# USB_OTG_FS.net
KiCad netlist of a schematic drawn in Altium Designer
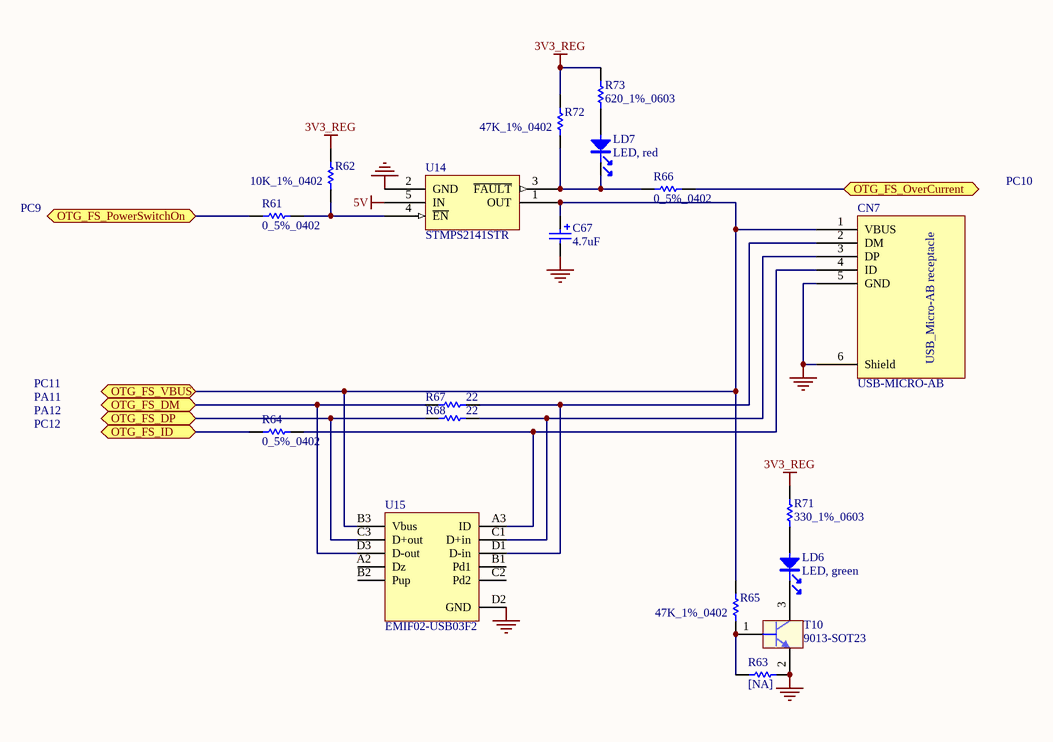
[diagram p0: USB_OTG_FS.SchDoc]

(export (version "E")
  (design (tool "Eeschema 10.0.6"))
  (components
    (comp (ref "C67")
      (value "4.7uF")
      (footprint "TAN-A")
      (description "Polarized Capacitor,4.7uF,16V,10%,typeA,AVX")
      (libsource (lib "MCD_TOOLS") (part "Cap_4.7uF_POL_10%_TANA"))
    )
    (comp (ref "CN7")
      (value "USB-MICRO-AB")
      (footprint "USB-MICRO-AB")
      (description "USB-MICRO-AB, 47590-0001, SMT, MOLEX")
      (libsource (lib "MCD_TOOLS") (part "USB-MICRO-AB"))
    )
    (comp (ref "LD6")
      (value "LED, green")
      (footprint "0603D")
      (description "LED,green,0603,19-213SYGC/S530-E2/TR8,everlight")
      (libsource (lib "MCD_TOOLS") (part "LED_green"))
    )
    (comp (ref "LD7")
      (value "LED, red")
      (footprint "0603D")
      (description "LED,red,0603,19-213-R6C-AP1Q2B/3T,everlight")
      (libsource (lib "MCD_TOOLS") (part "LED_red"))
    )
    (comp (ref "R61")
      (value "0_5%_0402")
      (footprint "0402R")
      (description "Resistor,0,0402,5%,YAGEO")
      (libsource (lib "MCD_TOOLS") (part "Res_0_5%_0402"))
    )
    (comp (ref "R62")
      (value "10K_1%_0402")
      (footprint "0402R")
      (description "Resistor,10K,0402,1%,YAGEO")
      (libsource (lib "MCD_TOOLS") (part "Res_10K_1%_0402"))
    )
    (comp (ref "R63")
      (value "[NA]")
      (footprint "0402R")
      (description "Resistor,[NA],0402")
      (libsource (lib "MCD_TOOLS") (part "Res_NA_0402"))
    )
    (comp (ref "R64")
      (value "0_5%_0402")
      (footprint "0402R")
      (description "Resistor,0,0402,5%,YAGEO")
      (libsource (lib "MCD_TOOLS") (part "Res_0_5%_0402"))
    )
    (comp (ref "R65")
      (value "47K_1%_0402")
      (footprint "0402R")
      (description "Resistor,47K,0402,1%,YAGEO")
      (libsource (lib "MCD_TOOLS") (part "Res_47K_1%_0402"))
    )
    (comp (ref "R66")
      (value "0_5%_0402")
      (footprint "0402R")
      (description "Resistor,0,0402,5%,YAGEO")
      (libsource (lib "MCD_TOOLS") (part "Res_0_5%_0402"))
    )
    (comp (ref "R67")
      (value "22")
      (footprint "0402R")
      (description "Resistor")
      (fields (field (name "PUBLISHER") "Altium Limited"))
      (libsource (lib "Miscellaneous Devices") (part "Res1"))
    )
    (comp (ref "R68")
      (value "22")
      (footprint "0402R")
      (description "Resistor")
      (fields (field (name "PUBLISHER") "Altium Limited"))
      (libsource (lib "Miscellaneous Devices") (part "Res1"))
    )
    (comp (ref "R71")
      (value "330_1%_0603")
      (footprint "0603R")
      (description "Resistor,330,0603,1%,YAGEO")
      (libsource (lib "MCD_TOOLS") (part "Res_330_1%_0603"))
    )
    (comp (ref "R72")
      (value "47K_1%_0402")
      (footprint "0402R")
      (description "Resistor,47K,0402,1%,YAGEO")
      (libsource (lib "MCD_TOOLS") (part "Res_47K_1%_0402"))
    )
    (comp (ref "R73")
      (value "620_1%_0603")
      (footprint "0603R")
      (description "Resistor,620,0603,1%,VISHAY")
      (libsource (lib "MCD_TOOLS") (part "Res_620_1%_0603"))
    )
    (comp (ref "T10")
      (value "9013-SOT23")
      (footprint "SOT23")
      (description "NPN Bipolar Transistor, SOT-23 Footprint")
      (libsource (lib "MCD_TOOLS") (part "9013-SOT23"))
    )
    (comp (ref "U14")
      (value "STMPS2141STR")
      (footprint "SOT23-5L")
      (description "Enhanced single channel power switches")
      (libsource (lib "MCD_TOOLS") (part "STMPS2141STR"))
    )
    (comp (ref "U15")
      (value "EMIF02-USB03F2")
      (footprint "Flip Chip")
      (description "2-line IPAD, EMI filter including ESD protection")
      (libsource (lib "MCD_TOOLS") (part "EMIF02-USB03F2"))
    )
  )
  (nets
    (net (code "1") (name "/OTG_FS_DM") (class "Default")
      (node (ref "R67") (pin "2") (pinfunction "2_2") (pintype "passive"))
      (node (ref "U15") (pin "D3") (pinfunction "D-out_D3") (pintype "passive"))
    )
    (net (code "2") (name "/OTG_FS_DP") (class "Default")
      (node (ref "R68") (pin "2") (pinfunction "2_2") (pintype "passive"))
      (node (ref "U15") (pin "C3") (pinfunction "D+out_C3") (pintype "passive"))
    )
    (net (code "3") (name "/OTG_FS_ID") (class "Default")
      (node (ref "R64") (pin "1") (pinfunction "1_1") (pintype "passive"))
    )
    (net (code "4") (name "/OTG_FS_OverCurrent") (class "Default")
      (node (ref "R66") (pin "2") (pinfunction "2_2") (pintype "passive"))
    )
    (net (code "5") (name "/OTG_FS_PowerSwitchOn") (class "Default")
      (node (ref "R61") (pin "1") (pinfunction "1_1") (pintype "passive"))
    )
    (net (code "6") (name "/OTG_FS_VBUS") (class "Default")
      (node (ref "C67") (pin "1") (pinfunction "1_1") (pintype "passive"))
      (node (ref "CN7") (pin "1") (pinfunction "VBUS_1") (pintype "passive"))
      (node (ref "R65") (pin "2") (pinfunction "2_2") (pintype "passive"))
      (node (ref "U14") (pin "1") (pinfunction "OUT_1") (pintype "passive"))
      (node (ref "U15") (pin "B3") (pinfunction "Vbus_B3") (pintype "passive"))
    )
    (net (code "7") (name "3V3_REG") (class "Default")
      (node (ref "R62") (pin "2") (pinfunction "2_2") (pintype "passive"))
      (node (ref "R71") (pin "2") (pinfunction "2_2") (pintype "passive"))
      (node (ref "R72") (pin "2") (pinfunction "2_2") (pintype "passive"))
      (node (ref "R73") (pin "2") (pinfunction "2_2") (pintype "passive"))
    )
    (net (code "8") (name "5V") (class "Default")
      (node (ref "U14") (pin "5") (pinfunction "IN_5") (pintype "passive"))
    )
    (net (code "9") (name "GND") (class "Default")
      (node (ref "C67") (pin "2") (pinfunction "2_2") (pintype "passive"))
      (node (ref "CN7") (pin "5") (pinfunction "GND_5") (pintype "passive"))
      (node (ref "CN7") (pin "6") (pinfunction "Shield_6") (pintype "passive"))
      (node (ref "R63") (pin "2") (pinfunction "2_2") (pintype "passive"))
      (node (ref "T10") (pin "2") (pinfunction "E_2") (pintype "passive"))
      (node (ref "U14") (pin "2") (pinfunction "GND_2") (pintype "passive"))
      (node (ref "U15") (pin "D2") (pinfunction "GND_D2") (pintype "passive"))
    )
    (net (code "10") (name "Net-(CN7-DM)") (class "Default")
      (node (ref "CN7") (pin "2") (pinfunction "DM_2") (pintype "passive"))
      (node (ref "R67") (pin "1") (pinfunction "1_1") (pintype "passive"))
      (node (ref "U15") (pin "D1") (pinfunction "D-in_D1") (pintype "passive"))
    )
    (net (code "11") (name "Net-(CN7-DP)") (class "Default")
      (node (ref "CN7") (pin "3") (pinfunction "DP_3") (pintype "passive"))
      (node (ref "R68") (pin "1") (pinfunction "1_1") (pintype "passive"))
      (node (ref "U15") (pin "C1") (pinfunction "D+in_C1") (pintype "passive"))
    )
    (net (code "12") (name "Net-(CN7-ID)") (class "Default")
      (node (ref "CN7") (pin "4") (pinfunction "ID_4") (pintype "passive"))
      (node (ref "R64") (pin "2") (pinfunction "2_2") (pintype "passive"))
      (node (ref "U15") (pin "A3") (pinfunction "ID_A3") (pintype "passive"))
    )
    (net (code "13") (name "Net-(LD6-Pad1)") (class "Default")
      (node (ref "LD6") (pin "1") (pintype "passive"))
      (node (ref "R71") (pin "1") (pinfunction "1_1") (pintype "passive"))
    )
    (net (code "14") (name "Net-(LD7-Pad1)") (class "Default")
      (node (ref "LD7") (pin "1") (pintype "passive"))
      (node (ref "R73") (pin "1") (pinfunction "1_1") (pintype "passive"))
    )
    (net (code "15") (name "Net-(T10-B)") (class "Default")
      (node (ref "R63") (pin "1") (pinfunction "1_1") (pintype "passive"))
      (node (ref "R65") (pin "1") (pinfunction "1_1") (pintype "passive"))
      (node (ref "T10") (pin "1") (pinfunction "B_1") (pintype "passive"))
    )
    (net (code "16") (name "Net-(T10-C)") (class "Default")
      (node (ref "LD6") (pin "2") (pintype "passive"))
      (node (ref "T10") (pin "3") (pinfunction "C_3") (pintype "passive"))
    )
    (net (code "17") (name "Net-(U14-~{EN})") (class "Default")
      (node (ref "R61") (pin "2") (pinfunction "2_2") (pintype "passive"))
      (node (ref "R62") (pin "1") (pinfunction "1_1") (pintype "passive"))
      (node (ref "U14") (pin "4") (pinfunction "~{EN}_4") (pintype "input"))
    )
    (net (code "18") (name "Net-(U14-~{FAULT})") (class "Default")
      (node (ref "LD7") (pin "2") (pintype "passive"))
      (node (ref "R66") (pin "1") (pinfunction "1_1") (pintype "passive"))
      (node (ref "R72") (pin "1") (pinfunction "1_1") (pintype "passive"))
      (node (ref "U14") (pin "3") (pinfunction "~{FAULT}_3") (pintype "output"))
    )
    (net (code "19") (name "unconnected-(U15-Dz-PadA2)") (class "Default")
      (node (ref "U15") (pin "A2") (pinfunction "Dz_A2") (pintype "passive"))
    )
    (net (code "20") (name "unconnected-(U15-Pd1-PadB1)") (class "Default")
      (node (ref "U15") (pin "B1") (pinfunction "Pd1_B1") (pintype "passive"))
    )
    (net (code "21") (name "unconnected-(U15-Pd2-PadC2)") (class "Default")
      (node (ref "U15") (pin "C2") (pinfunction "Pd2_C2") (pintype "passive"))
    )
    (net (code "22") (name "unconnected-(U15-Pup-PadB2)") (class "Default")
      (node (ref "U15") (pin "B2") (pinfunction "Pup_B2") (pintype "passive"))
    )
  )
)
